# PCB_midrat_v1.net
KiCad netlist of a schematic drawn in EAGLE
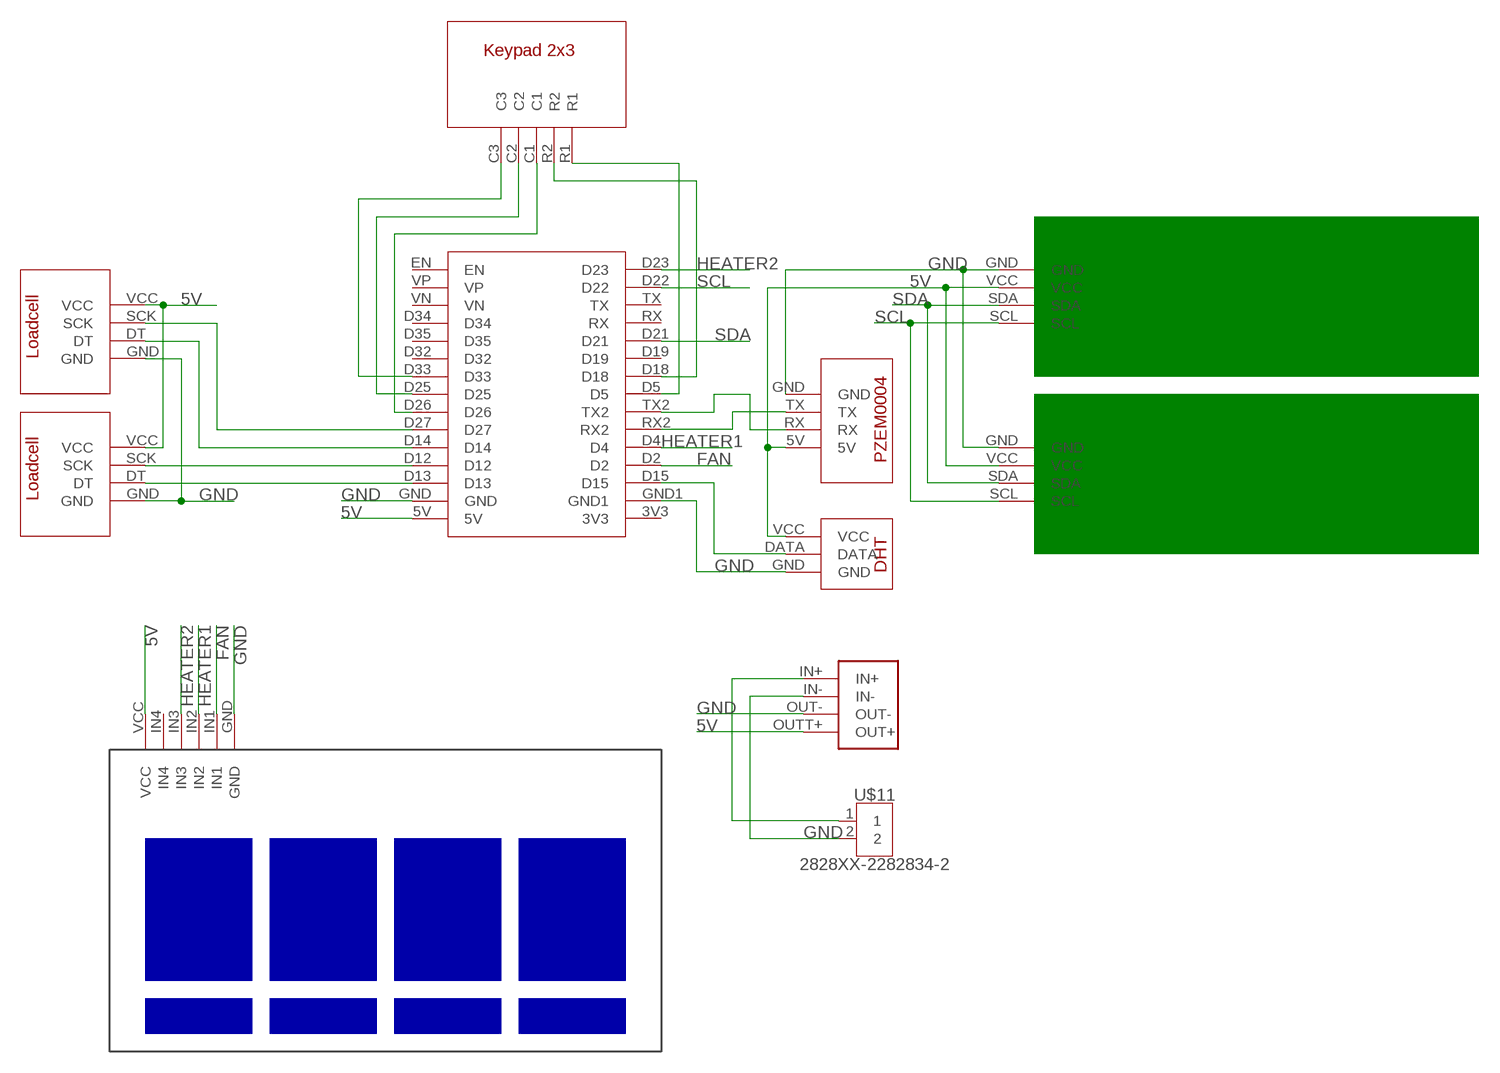
[diagram p0: schematic, sheet 1]

(export (version "E")
  (design (tool "Eeschema 10.0.6"))
  (components
    (comp (ref "U$1")
      (value "ESP32_30PIN")
      (footprint "eagle-import:ESP32_30PIN")
      (libsource (lib "eagle-import") (part "ESP32_30PIN"))
    )
    (comp (ref "U$2")
      (value "KEYPAD_2X3")
      (footprint "eagle-import:KEYPAD2X3")
      (libsource (lib "eagle-import") (part "KEYPAD_2X3"))
    )
    (comp (ref "U$3")
      (value "LCD_I2C")
      (footprint "eagle-import:LCD_I2C")
      (libsource (lib "eagle-import") (part "LCD_I2C"))
    )
    (comp (ref "U$4")
      (value "LOADCELL")
      (footprint "eagle-import:LOADCELL")
      (libsource (lib "eagle-import") (part "LOADCELL"))
    )
    (comp (ref "U$5")
      (value "PZEM0004")
      (footprint "eagle-import:PZEM0004")
      (libsource (lib "eagle-import") (part "PZEM0004"))
    )
    (comp (ref "U$6")
      (value "RELAY_4CHANNEL")
      (footprint "eagle-import:RELAY_4CHANNEL")
      (libsource (lib "eagle-import") (part "RELAY_4CHANNEL"))
    )
    (comp (ref "U$7")
      (value "LOADCELL")
      (footprint "eagle-import:LOADCELL")
      (libsource (lib "eagle-import") (part "LOADCELL"))
    )
    (comp (ref "U$8")
      (value "LCD_I2C")
      (footprint "eagle-import:LCD_I2C")
      (libsource (lib "eagle-import") (part "LCD_I2C"))
    )
    (comp (ref "U$9")
      (value "XL4005E1")
      (footprint "eagle-import:XL4005E1")
      (libsource (lib "eagle-import") (part "XL4005E1"))
    )
    (comp (ref "U$10")
      (value "DHT")
      (footprint "eagle-import:DHT")
      (libsource (lib "eagle-import") (part "DHT"))
    )
    (comp (ref "U$11")
      (value "2828XX-2282834-2")
      (footprint "eagle-import:TERMBLK_254-2N")
      (libsource (lib "eagle-import") (part "2828XX-2282834-2"))
    )
  )
  (nets
    (net (code "1") (name "/5V") (class "Default")
      (node (ref "U$1") (pin "5V") (pinfunction "5V_5V") (pintype "bidirectional"))
      (node (ref "U$10") (pin "VCC") (pinfunction "VCC_VCC") (pintype "bidirectional"))
      (node (ref "U$3") (pin "VCC") (pinfunction "VCC_VCC") (pintype "bidirectional"))
      (node (ref "U$4") (pin "VCC") (pinfunction "VCC_VCC") (pintype "bidirectional"))
      (node (ref "U$5") (pin "5V") (pinfunction "5V_5V") (pintype "bidirectional"))
      (node (ref "U$6") (pin "VCC") (pinfunction "VCC_VCC") (pintype "bidirectional"))
      (node (ref "U$7") (pin "VCC") (pinfunction "VCC_VCC") (pintype "bidirectional"))
      (node (ref "U$8") (pin "VCC") (pinfunction "VCC_VCC") (pintype "bidirectional"))
      (node (ref "U$9") (pin "OUTT+") (pinfunction "OUT+_OUTT+") (pintype "bidirectional"))
    )
    (net (code "2") (name "/FAN") (class "Default")
      (node (ref "U$1") (pin "D2") (pinfunction "D2_D2") (pintype "bidirectional"))
      (node (ref "U$6") (pin "IN1") (pinfunction "IN1_IN1") (pintype "bidirectional"))
    )
    (net (code "3") (name "/GND") (class "Default")
      (node (ref "U$1") (pin "GND") (pinfunction "GND_GND") (pintype "bidirectional"))
      (node (ref "U$1") (pin "GND1") (pinfunction "GND1_GND1") (pintype "bidirectional"))
      (node (ref "U$10") (pin "GND") (pinfunction "GND_GND") (pintype "bidirectional"))
      (node (ref "U$11") (pin "2") (pinfunction "2_2") (pintype "bidirectional"))
      (node (ref "U$3") (pin "GND") (pinfunction "GND_GND") (pintype "bidirectional"))
      (node (ref "U$4") (pin "GND") (pinfunction "GND_GND") (pintype "bidirectional"))
      (node (ref "U$5") (pin "GND") (pinfunction "GND_GND") (pintype "bidirectional"))
      (node (ref "U$6") (pin "GND") (pinfunction "GND_GND") (pintype "bidirectional"))
      (node (ref "U$7") (pin "GND") (pinfunction "GND_GND") (pintype "bidirectional"))
      (node (ref "U$8") (pin "GND") (pinfunction "GND_GND") (pintype "bidirectional"))
      (node (ref "U$9") (pin "IN-") (pinfunction "IN-_IN-") (pintype "bidirectional"))
      (node (ref "U$9") (pin "OUT-") (pinfunction "OUT-_OUT-") (pintype "bidirectional"))
    )
    (net (code "4") (name "/HEATER1") (class "Default")
      (node (ref "U$1") (pin "D4") (pinfunction "D4_D4") (pintype "bidirectional"))
      (node (ref "U$6") (pin "IN2") (pinfunction "IN2_IN2") (pintype "bidirectional"))
    )
    (net (code "5") (name "/HEATER2") (class "Default")
      (node (ref "U$1") (pin "D23") (pinfunction "D23_D23") (pintype "bidirectional"))
      (node (ref "U$6") (pin "IN3") (pinfunction "IN3_IN3") (pintype "bidirectional"))
    )
    (net (code "6") (name "/SCL") (class "Default")
      (node (ref "U$1") (pin "D22") (pinfunction "D22_D22") (pintype "bidirectional"))
      (node (ref "U$3") (pin "SCL") (pinfunction "SCL_SCL") (pintype "bidirectional"))
      (node (ref "U$8") (pin "SCL") (pinfunction "SCL_SCL") (pintype "bidirectional"))
    )
    (net (code "7") (name "/SDA") (class "Default")
      (node (ref "U$1") (pin "D21") (pinfunction "D21_D21") (pintype "bidirectional"))
      (node (ref "U$3") (pin "SDA") (pinfunction "SDA_SDA") (pintype "bidirectional"))
      (node (ref "U$8") (pin "SDA") (pinfunction "SDA_SDA") (pintype "bidirectional"))
    )
    (net (code "8") (name "Net-(U$1-PadD5)") (class "Default")
      (node (ref "U$1") (pin "D5") (pinfunction "D5_D5") (pintype "bidirectional"))
      (node (ref "U$2") (pin "R1") (pinfunction "R1_R1") (pintype "bidirectional"))
    )
    (net (code "9") (name "Net-(U$1-PadD12)") (class "Default")
      (node (ref "U$1") (pin "D12") (pinfunction "D12_D12") (pintype "bidirectional"))
      (node (ref "U$4") (pin "SCK") (pinfunction "SCK_SCK") (pintype "bidirectional"))
    )
    (net (code "10") (name "Net-(U$1-PadD13)") (class "Default")
      (node (ref "U$1") (pin "D13") (pinfunction "D13_D13") (pintype "bidirectional"))
      (node (ref "U$4") (pin "DT") (pinfunction "DT_DT") (pintype "bidirectional"))
    )
    (net (code "11") (name "Net-(U$1-PadD14)") (class "Default")
      (node (ref "U$1") (pin "D14") (pinfunction "D14_D14") (pintype "bidirectional"))
      (node (ref "U$7") (pin "DT") (pinfunction "DT_DT") (pintype "bidirectional"))
    )
    (net (code "12") (name "Net-(U$1-PadD15)") (class "Default")
      (node (ref "U$1") (pin "D15") (pinfunction "D15_D15") (pintype "bidirectional"))
      (node (ref "U$10") (pin "DATA") (pinfunction "DATA_DATA") (pintype "bidirectional"))
    )
    (net (code "13") (name "Net-(U$1-PadD18)") (class "Default")
      (node (ref "U$1") (pin "D18") (pinfunction "D18_D18") (pintype "bidirectional"))
      (node (ref "U$2") (pin "R2") (pinfunction "R2_R2") (pintype "bidirectional"))
    )
    (net (code "14") (name "Net-(U$1-PadD25)") (class "Default")
      (node (ref "U$1") (pin "D25") (pinfunction "D25_D25") (pintype "bidirectional"))
      (node (ref "U$2") (pin "C2") (pinfunction "C2_C2") (pintype "bidirectional"))
    )
    (net (code "15") (name "Net-(U$1-PadD26)") (class "Default")
      (node (ref "U$1") (pin "D26") (pinfunction "D26_D26") (pintype "bidirectional"))
      (node (ref "U$2") (pin "C1") (pinfunction "C1_C1") (pintype "bidirectional"))
    )
    (net (code "16") (name "Net-(U$1-PadD27)") (class "Default")
      (node (ref "U$1") (pin "D27") (pinfunction "D27_D27") (pintype "bidirectional"))
      (node (ref "U$7") (pin "SCK") (pinfunction "SCK_SCK") (pintype "bidirectional"))
    )
    (net (code "17") (name "Net-(U$1-PadD33)") (class "Default")
      (node (ref "U$1") (pin "D33") (pinfunction "D33_D33") (pintype "bidirectional"))
      (node (ref "U$2") (pin "C3") (pinfunction "C3_C3") (pintype "bidirectional"))
    )
    (net (code "18") (name "Net-(U$1-PadRX2)") (class "Default")
      (node (ref "U$1") (pin "RX2") (pinfunction "RX2_RX2") (pintype "bidirectional"))
      (node (ref "U$5") (pin "TX") (pinfunction "TX_TX") (pintype "bidirectional"))
    )
    (net (code "19") (name "Net-(U$1-PadTX2)") (class "Default")
      (node (ref "U$1") (pin "TX2") (pinfunction "TX2_TX2") (pintype "bidirectional"))
      (node (ref "U$5") (pin "RX") (pinfunction "RX_RX") (pintype "bidirectional"))
    )
    (net (code "20") (name "Net-(U$11-Pad1)") (class "Default")
      (node (ref "U$11") (pin "1") (pinfunction "1_1") (pintype "bidirectional"))
      (node (ref "U$9") (pin "IN+") (pinfunction "IN+_IN+") (pintype "bidirectional"))
    )
    (net (code "21") (name "unconnected-(U$1-Pad3V3)") (class "Default")
      (node (ref "U$1") (pin "3V3") (pinfunction "3V3_3V3") (pintype "bidirectional"))
    )
    (net (code "22") (name "unconnected-(U$1-PadD19)") (class "Default")
      (node (ref "U$1") (pin "D19") (pinfunction "D19_D19") (pintype "bidirectional"))
    )
    (net (code "23") (name "unconnected-(U$1-PadD32)") (class "Default")
      (node (ref "U$1") (pin "D32") (pinfunction "D32_D32") (pintype "bidirectional"))
    )
    (net (code "24") (name "unconnected-(U$1-PadD34)") (class "Default")
      (node (ref "U$1") (pin "D34") (pinfunction "D34_D34") (pintype "bidirectional"))
    )
    (net (code "25") (name "unconnected-(U$1-PadD35)") (class "Default")
      (node (ref "U$1") (pin "D35") (pinfunction "D35_D35") (pintype "bidirectional"))
    )
    (net (code "26") (name "unconnected-(U$1-PadEN)") (class "Default")
      (node (ref "U$1") (pin "EN") (pinfunction "EN_EN") (pintype "bidirectional"))
    )
    (net (code "27") (name "unconnected-(U$1-PadRX)") (class "Default")
      (node (ref "U$1") (pin "RX") (pinfunction "RX_RX") (pintype "bidirectional"))
    )
    (net (code "28") (name "unconnected-(U$1-PadTX)") (class "Default")
      (node (ref "U$1") (pin "TX") (pinfunction "TX_TX") (pintype "bidirectional"))
    )
    (net (code "29") (name "unconnected-(U$1-PadVN)") (class "Default")
      (node (ref "U$1") (pin "VN") (pinfunction "VN_VN") (pintype "bidirectional"))
    )
    (net (code "30") (name "unconnected-(U$1-PadVP)") (class "Default")
      (node (ref "U$1") (pin "VP") (pinfunction "VP_VP") (pintype "bidirectional"))
    )
    (net (code "31") (name "unconnected-(U$6-PadIN4)") (class "Default")
      (node (ref "U$6") (pin "IN4") (pinfunction "IN4_IN4") (pintype "bidirectional"))
    )
  )
)
